# Sheet1.net
KiCad netlist of a schematic drawn in Altium Designer
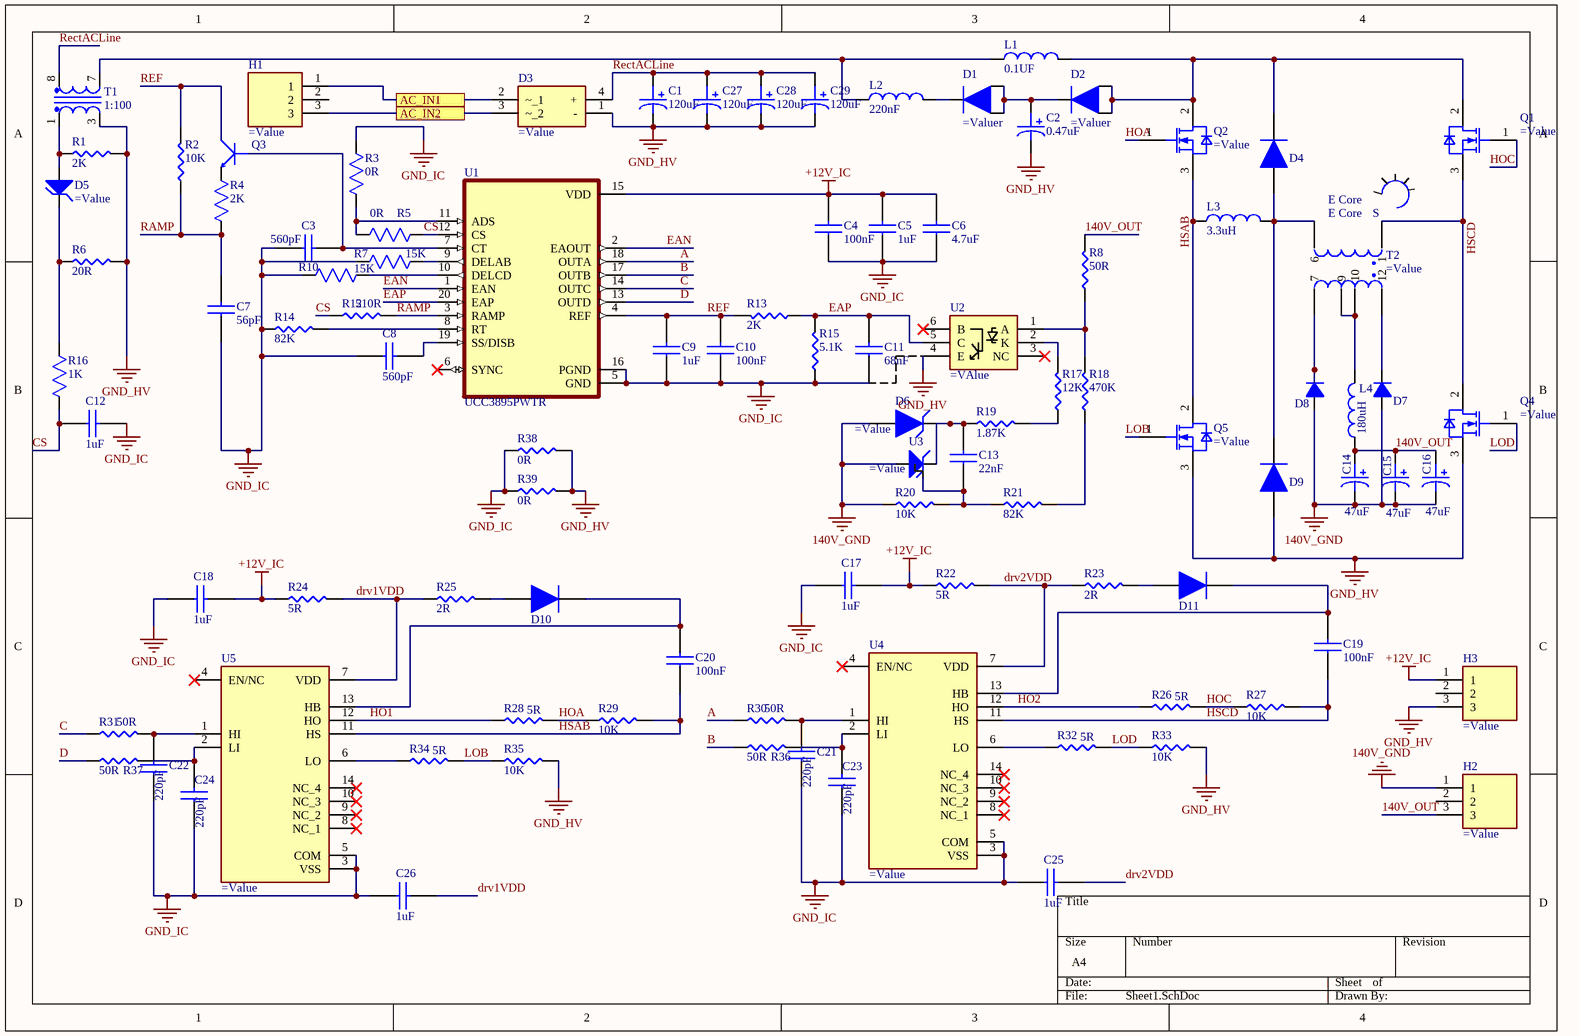
[diagram p0: Sheet1.SchDoc]

(export (version "E")
  (design (tool "Eeschema 10.0.6"))
  (components
    (comp (ref "C1")
      (value "120uF")
      (footprint "18AL_CAP")
      (description "120 µF 400 V Aluminum Electrolytic Capacitors Radial, Can 12000 Hrs @ 105°C")
      (fields
        (field (name "MANUFACTURER") "Nichicon")
        (field (name "MANUFACTURER PART NUMBER") "EEV686M035A9HAA")
      )
      (libsource (lib "Yunus") (part "CAP_Pol"))
    )
    (comp (ref "C2")
      (value "0.47uF")
      (footprint "860021373001_PCB")
      (description "0.47 µF 400 V Aluminum Electrolytic Capacitors Radial, Can 2000 Hrs @ 105°C")
      (fields
        (field (name "MANUFACTURER") "Würth Elektronik")
        (field (name "MANUFACTURER PART NUMBER") "EEV686M035A9HAA")
      )
      (libsource (lib "Yunus") (part "CAP_Pol"))
    )
    (comp (ref "C3")
      (value "560pF")
      (footprint "CAP_0805")
      (description "Cap.,SMD,0805,NP0,560pF,5%,100V")
      (fields
        (field (name "MANUFACTURER") "Aillen")
        (field (name "MANUFACTURER PART NUMBER") "CL21B105KBFNNNE")
        (field (name "DESIGNED BY") "BERK")
      )
      (libsource (lib "Yunus") (part "CAP_non"))
    )
    (comp (ref "C4")
      (value "100nF")
      (footprint "CAP_0805")
      (description "Auto. MLCC X7R 100nF 10% 100V 08")
      (fields
        (field (name "MANUFACTURER") "EYang Technology")
        (field (name "MANUFACTURER PART NUMBER") "CL21B105KBFNNNE")
        (field (name "DESIGNED BY") "BERK")
      )
      (libsource (lib "Yunus") (part "CAP_non"))
    )
    (comp (ref "C5")
      (value "1uF")
      (footprint "CAP_0805")
      (description "CAP SMD,0805,X7R,1UF,10%,50V")
      (fields
        (field (name "MANUFACTURER") "Aillen")
        (field (name "MANUFACTURER PART NUMBER") "CL21B105KBFNNNE")
        (field (name "DESIGNED BY") "BERK")
      )
      (libsource (lib "Yunus") (part "CAP_non"))
    )
    (comp (ref "C6")
      (value "4.7uF")
      (footprint "CAP_0805")
      (description "CAP,SMD,0805,X7R,4.7UF,10%,25V")
      (fields
        (field (name "MANUFACTURER") "NextGen Components")
        (field (name "MANUFACTURER PART NUMBER") "CL21B105KBFNNNE")
        (field (name "DESIGNED BY") "BERK")
      )
      (libsource (lib "Yunus") (part "CAP_non"))
    )
    (comp (ref "C7")
      (value "56pF")
      (footprint "CAP_0805")
      (description "CAP,SMD,0805,NP0,56PF,5%,50V")
      (fields
        (field (name "MANUFACTURER") "NextGen Components")
        (field (name "MANUFACTURER PART NUMBER") "CL21B105KBFNNNE")
        (field (name "DESIGNED BY") "BERK")
      )
      (libsource (lib "Yunus") (part "CAP_non"))
    )
    (comp (ref "C8")
      (value "560pF")
      (footprint "CAP_0805")
      (description "Cap.,SMD,0805,NP0,560pF,5%,100V")
      (fields
        (field (name "MANUFACTURER") "Aillen")
        (field (name "MANUFACTURER PART NUMBER") "CL21B105KBFNNNE")
        (field (name "DESIGNED BY") "BERK")
      )
      (libsource (lib "Yunus") (part "CAP_non"))
    )
    (comp (ref "C9")
      (value "1uF")
      (footprint "CAP_0805")
      (description "CAP SMD,0805,X7R,1UF,10%,50V")
      (fields
        (field (name "MANUFACTURER") "Aillen")
        (field (name "MANUFACTURER PART NUMBER") "CL21B105KBFNNNE")
        (field (name "DESIGNED BY") "BERK")
      )
      (libsource (lib "Yunus") (part "CAP_non"))
    )
    (comp (ref "C10")
      (value "100nF")
      (footprint "CAP_0805")
      (description "Auto. MLCC X7R 100nF 10% 100V 08")
      (fields
        (field (name "MANUFACTURER") "EYang Technology")
        (field (name "MANUFACTURER PART NUMBER") "CL21B105KBFNNNE")
        (field (name "DESIGNED BY") "BERK")
      )
      (libsource (lib "Yunus") (part "CAP_non"))
    )
    (comp (ref "C11")
      (value "68nF")
      (footprint "CAP_0805")
      (description "CAP CER 0805 68NF 50V X7R 10%")
      (fields
        (field (name "MANUFACTURER") "KEMET")
        (field (name "MANUFACTURER PART NUMBER") "CL21B105KBFNNNE")
        (field (name "DESIGNED BY") "BERK")
      )
      (libsource (lib "Yunus") (part "CAP_non"))
    )
    (comp (ref "C12")
      (value "1uF")
      (footprint "CAP_0805")
      (description "CAP SMD,0805,X7R,1UF,10%,50V")
      (fields
        (field (name "MANUFACTURER") "Aillen")
        (field (name "MANUFACTURER PART NUMBER") "CL21B105KBFNNNE")
        (field (name "DESIGNED BY") "BERK")
      )
      (libsource (lib "Yunus") (part "CAP_non"))
    )
    (comp (ref "C13")
      (value "22nF")
      (footprint "CAP_0805")
      (description "CAP CER 0805 22NF 200V X7R 10%")
      (fields
        (field (name "MANUFACTURER") "KEMET")
        (field (name "MANUFACTURER PART NUMBER") "CL21B105KBFNNNE")
        (field (name "DESIGNED BY") "BERK")
      )
      (libsource (lib "Yunus") (part "CAP_non"))
    )
    (comp (ref "C14")
      (value "47uF")
      (footprint "CAP200V47uF")
      (description "CAP ALUM 47UF 20% 200V RADIAL TH")
      (fields
        (field (name "MANUFACTURER") "KYOCERA AVX")
        (field (name "MANUFACTURER PART NUMBER") "EEV686M035A9HAA")
      )
      (libsource (lib "Yunus") (part "CAP_Pol"))
    )
    (comp (ref "C15")
      (value "47uF")
      (footprint "CAP200V47uF")
      (description "CAP ALUM 47UF 20% 200V RADIAL TH")
      (fields
        (field (name "MANUFACTURER") "KYOCERA AVX")
        (field (name "MANUFACTURER PART NUMBER") "EEV686M035A9HAA")
      )
      (libsource (lib "Yunus") (part "CAP_Pol"))
    )
    (comp (ref "C16")
      (value "47uF")
      (footprint "CAP200V47uF")
      (description "CAP ALUM 47UF 20% 200V RADIAL TH")
      (fields
        (field (name "MANUFACTURER") "KYOCERA AVX")
        (field (name "MANUFACTURER PART NUMBER") "EEV686M035A9HAA")
      )
      (libsource (lib "Yunus") (part "CAP_Pol"))
    )
    (comp (ref "C17")
      (value "1uF")
      (footprint "CAP_0805")
      (description "CAP SMD,0805,X7R,1UF,10%,50V")
      (fields
        (field (name "MANUFACTURER") "Aillen")
        (field (name "MANUFACTURER PART NUMBER") "CL21B105KBFNNNE")
        (field (name "DESIGNED BY") "BERK")
      )
      (libsource (lib "Yunus") (part "CAP_non"))
    )
    (comp (ref "C18")
      (value "1uF")
      (footprint "CAP_0805")
      (description "CAP SMD,0805,X7R,1UF,10%,50V")
      (fields
        (field (name "MANUFACTURER") "Aillen")
        (field (name "MANUFACTURER PART NUMBER") "CL21B105KBFNNNE")
        (field (name "DESIGNED BY") "BERK")
      )
      (libsource (lib "Yunus") (part "CAP_non"))
    )
    (comp (ref "C19")
      (value "100nF")
      (footprint "CAP_0805")
      (description "Auto. MLCC X7R 100nF 10% 100V 08")
      (fields
        (field (name "MANUFACTURER") "EYang Technology")
        (field (name "MANUFACTURER PART NUMBER") "CL21B105KBFNNNE")
        (field (name "DESIGNED BY") "BERK")
      )
      (libsource (lib "Yunus") (part "CAP_non"))
    )
    (comp (ref "C20")
      (value "100nF")
      (footprint "CAP_0805")
      (description "Auto. MLCC X7R 100nF 10% 100V 08")
      (fields
        (field (name "MANUFACTURER") "EYang Technology")
        (field (name "MANUFACTURER PART NUMBER") "CL21B105KBFNNNE")
        (field (name "DESIGNED BY") "BERK")
      )
      (libsource (lib "Yunus") (part "CAP_non"))
    )
    (comp (ref "C21")
      (value "220pF")
      (footprint "CAP_0805")
      (description "CAP CER 220PF 250V C0G/NP0 0805")
      (fields
        (field (name "MANUFACTURER") "KYOCERA AVX")
        (field (name "MANUFACTURER PART NUMBER") "CL21B105KBFNNNE")
        (field (name "DESIGNED BY") "BERK")
      )
      (libsource (lib "Yunus") (part "CAP_non"))
    )
    (comp (ref "C22")
      (value "220pF")
      (footprint "CAP_0805")
      (description "CAP CER 220PF 250V C0G/NP0 0805")
      (fields
        (field (name "MANUFACTURER") "KYOCERA AVX")
        (field (name "MANUFACTURER PART NUMBER") "CL21B105KBFNNNE")
        (field (name "DESIGNED BY") "BERK")
      )
      (libsource (lib "Yunus") (part "CAP_non"))
    )
    (comp (ref "C23")
      (value "220pF")
      (footprint "CAP_0805")
      (description "CAP CER 220PF 250V C0G/NP0 0805")
      (fields
        (field (name "MANUFACTURER") "KYOCERA AVX")
        (field (name "MANUFACTURER PART NUMBER") "CL21B105KBFNNNE")
        (field (name "DESIGNED BY") "BERK")
      )
      (libsource (lib "Yunus") (part "CAP_non"))
    )
    (comp (ref "C24")
      (value "220pF")
      (footprint "CAP_0805")
      (description "CAP CER 220PF 250V C0G/NP0 0805")
      (fields
        (field (name "MANUFACTURER") "KYOCERA AVX")
        (field (name "MANUFACTURER PART NUMBER") "CL21B105KBFNNNE")
        (field (name "DESIGNED BY") "BERK")
      )
      (libsource (lib "Yunus") (part "CAP_non"))
    )
    (comp (ref "C25")
      (value "1uF")
      (footprint "CAP_0805")
      (description "CAP SMD,0805,X7R,1UF,10%,50V")
      (fields
        (field (name "MANUFACTURER") "Aillen")
        (field (name "MANUFACTURER PART NUMBER") "CL21B105KBFNNNE")
        (field (name "DESIGNED BY") "BERK")
      )
      (libsource (lib "Yunus") (part "CAP_non"))
    )
    (comp (ref "C26")
      (value "1uF")
      (footprint "CAP_0805")
      (description "CAP SMD,0805,X7R,1UF,10%,50V")
      (fields
        (field (name "MANUFACTURER") "Aillen")
        (field (name "MANUFACTURER PART NUMBER") "CL21B105KBFNNNE")
        (field (name "DESIGNED BY") "BERK")
      )
      (libsource (lib "Yunus") (part "CAP_non"))
    )
    (comp (ref "C27")
      (value "120uF")
      (footprint "18AL_CAP")
      (description "120 µF 400 V Aluminum Electrolytic Capacitors Radial, Can 12000 Hrs @ 105°C")
      (fields
        (field (name "MANUFACTURER") "Nichicon")
        (field (name "MANUFACTURER PART NUMBER") "EEV686M035A9HAA")
      )
      (libsource (lib "Yunus") (part "CAP_Pol"))
    )
    (comp (ref "C28")
      (value "120uF")
      (footprint "18AL_CAP")
      (description "120 µF 400 V Aluminum Electrolytic Capacitors Radial, Can 12000 Hrs @ 105°C")
      (fields
        (field (name "MANUFACTURER") "Nichicon")
        (field (name "MANUFACTURER PART NUMBER") "EEV686M035A9HAA")
      )
      (libsource (lib "Yunus") (part "CAP_Pol"))
    )
    (comp (ref "C29")
      (value "120uF")
      (footprint "18AL_CAP")
      (description "120 µF 400 V Aluminum Electrolytic Capacitors Radial, Can 12000 Hrs @ 105°C")
      (fields
        (field (name "MANUFACTURER") "Nichicon")
        (field (name "MANUFACTURER PART NUMBER") "EEV686M035A9HAA")
      )
      (libsource (lib "Yunus") (part "CAP_Pol"))
    )
    (comp (ref "D1")
      (value "~")
      (footprint "DPAK(TO-252-2)")
      (description "DIODE STANDARD 600V 20A DPAK")
      (fields (field (name "MANUFACTURER") "SMC Diode Solutions"))
      (libsource (lib "Yunus") (part "DIODE(DPAC)"))
    )
    (comp (ref "D2")
      (value "~")
      (footprint "DPAK(TO-252-2)")
      (description "DIODE STANDARD 600V 20A DPAK")
      (fields (field (name "MANUFACTURER") "SMC Diode Solutions"))
      (libsource (lib "Yunus") (part "DIODE(DPAC)"))
    )
    (comp (ref "D3")
      (value "~")
      (footprint "4-SIP")
      (description "Bridge Rectifier Single Phase Standard 1 kV Through Hole GBU")
      (fields (field (name "MANUFACTURER") "MCC (Micro Commercial Components)"))
      (libsource (lib "Yunus") (part "Diode_Rectifire"))
    )
    (comp (ref "D4")
      (value "~")
      (footprint "DO-214AB(SMC)")
      (description "Diode 600 V 3A Surface Mount SMC")
      (fields (field (name "MANUFACTURER") "onsemi") (field (name "DESIGNED BY") "Yunus"))
      (libsource (lib "Yunus") (part "Diode"))
    )
    (comp (ref "D5")
      (value "~")
      (footprint "SOD123")
      (description "Diode 30 V 200mA Surface Mount SOD-123")
      (fields (field (name "MANUFACTURER") "onsemi"))
      (libsource (lib "Yunus") (part "TVS Diode"))
    )
    (comp (ref "D6")
      (value "~")
      (footprint "DO_214AA")
      (description "DIODE ZENER 140V 5W DO214AA")
      (fields
        (field (name "MANUFACTURER") "MCC (Micro Commercial Components)")
        (field (name "MANUFACTURER PART NUMBER") "9BT3G")
      )
      (libsource (lib "Yunus") (part "Zener Diode"))
    )
    (comp (ref "D7")
      (value "~")
      (footprint "DPAK(TO-252-2)")
      (description "DIODE SCHOTTKY 1200V 5A DPAK")
      (fields (field (name "MANUFACTURER") "SMC Diode Solutions"))
      (libsource (lib "Yunus") (part "S4D05120E1(SCHOTTKY Diode)"))
    )
    (comp (ref "D8")
      (value "~")
      (footprint "DPAK(TO-252-2)")
      (description "DIODE SCHOTTKY 1200V 5A DPAK")
      (fields (field (name "MANUFACTURER") "SMC Diode Solutions"))
      (libsource (lib "Yunus") (part "S4D05120E1(SCHOTTKY Diode)"))
    )
    (comp (ref "D9")
      (value "~")
      (footprint "DO-214AB(SMC)")
      (description "Diode 600 V 3A Surface Mount SMC")
      (fields (field (name "MANUFACTURER") "onsemi") (field (name "DESIGNED BY") "Yunus"))
      (libsource (lib "Yunus") (part "Diode"))
    )
    (comp (ref "D10")
      (value "~")
      (footprint "DO-214AB(SMC)")
      (description "Diode 600 V 3A Surface Mount SMC")
      (fields (field (name "MANUFACTURER") "onsemi") (field (name "DESIGNED BY") "Yunus"))
      (libsource (lib "Yunus") (part "Diode"))
    )
    (comp (ref "D11")
      (value "~")
      (footprint "DO-214AB(SMC)")
      (description "Diode 600 V 3A Surface Mount SMC")
      (fields (field (name "MANUFACTURER") "onsemi") (field (name "DESIGNED BY") "Yunus"))
      (libsource (lib "Yunus") (part "Diode"))
    )
    (comp (ref "H1")
      (value "~")
      (footprint "3 x 5.08 POS")
      (description "TERM BLOCK HDR 3POS 5.08MM")
      (fields (field (name "MANUFACTURER") "Same Sky (Formerly CUI Devices)"))
      (libsource (lib "") (part "3 X POS_1"))
    )
    (comp (ref "H2")
      (value "~")
      (footprint "3 x 5.08 POS")
      (description "TERM BLOCK HDR 3POS 5.08MM")
      (fields (field (name "MANUFACTURER") "Same Sky (Formerly CUI Devices)"))
      (libsource (lib "Yunus") (part "3 X POS"))
    )
    (comp (ref "H3")
      (value "~")
      (footprint "3 x 5.08 POS")
      (description "TERM BLOCK HDR 3POS 5.08MM")
      (fields (field (name "MANUFACTURER") "Same Sky (Formerly CUI Devices)"))
      (libsource (lib "Yunus") (part "3 X POS"))
    )
    (comp (ref "L1")
      (value "0.1UF")
      (footprint "7.30mm x 6.60mm")
      (description "100 nH Shielded Wirewound Inductor 37.5 A 1.7mOhm Max Nonstandard")
      (fields (field (name "MANUFACTURER") "Bourns Inc."))
      (libsource (lib "Yunus") (part "Enductance"))
    )
    (comp (ref "L2")
      (value "220nF")
      (footprint "7.30mm x 6.60mm")
      (description "220 nH Shielded Molded Inductor 23 A 2.8mOhm Max Nonstandard")
      (fields (field (name "MANUFACTURER") "Pulse Electronics"))
      (libsource (lib "Yunus") (part "Enductance"))
    )
    (comp (ref "L3")
      (value "3.3uH")
      (footprint "14.4MOHM SMD")
      (description "FIXED IND 3.3UH 10A 14.4MOHM SMD")
      (fields (field (name "MANUFACTURER") "Vishay Dale"))
      (libsource (lib "Yunus") (part "Enductance"))
    )
    (comp (ref "L4")
      (value "180uH")
      (footprint "2300HT-181-V-RC")
      (description "180 µH Shielded Toroidal Inductor 7.2 A 55mOhm Max Radial, Vertical (Open)")
      (fields (field (name "MANUFACTURER") "Bourns Inc."))
      (libsource (lib "Yunus") (part "Enductance"))
    )
    (comp (ref "Q1")
      (value "~")
      (footprint "TO220")
      (description "N-Channel 650 V 25A (Tc) 32W (Tc) Through Hole PG-TO220-FP")
      (fields (field (name "MANUFACTURER") "Infineon Technologies"))
      (libsource (lib "Yunus") (part "N_MOS"))
    )
    (comp (ref "Q2")
      (value "~")
      (footprint "TO220")
      (description "N-Channel 650 V 25A (Tc) 32W (Tc) Through Hole PG-TO220-FP")
      (fields (field (name "MANUFACTURER") "Infineon Technologies"))
      (libsource (lib "Yunus") (part "N_MOS"))
    )
    (comp (ref "Q3")
      (value "~")
      (footprint "SOT-23-3")
      (description "TRANS NPN 80V 0.5A SOT-23-3")
      (fields (field (name "MANUFACTURER") "Diodes Incorporated") (field (name "DESIGNED BY") "YYunus"))
      (libsource (lib "Yunus") (part "NPN Transistor"))
    )
    (comp (ref "Q4")
      (value "~")
      (footprint "TO220")
      (description "N-Channel 650 V 25A (Tc) 32W (Tc) Through Hole PG-TO220-FP")
      (fields (field (name "MANUFACTURER") "Infineon Technologies"))
      (libsource (lib "Yunus") (part "N_MOS"))
    )
    (comp (ref "Q5")
      (value "~")
      (footprint "TO220")
      (description "N-Channel 650 V 25A (Tc) 32W (Tc) Through Hole PG-TO220-FP")
      (fields (field (name "MANUFACTURER") "Infineon Technologies"))
      (libsource (lib "Yunus") (part "N_MOS"))
    )
    (comp (ref "R1")
      (value "2K")
      (footprint "RES_0805")
      (description "RES SMD 2K OHM 0.1% 1/8W 0805")
      (fields (field (name "MANUFACTURER") "Panasonic Electronic Components"))
      (libsource (lib "Yunus") (part "RES"))
    )
    (comp (ref "R2")
      (value "10K")
      (footprint "RES_0805")
      (description "RES SMD 10K OHM 0.5% 1/10W 0805")
      (fields (field (name "MANUFACTURER") "Susumu"))
      (libsource (lib "Yunus") (part "RES"))
    )
    (comp (ref "R3")
      (value "0R")
      (footprint "RES_0805")
      (description "RES SMD 0 OHM JUMPER 1/8W 0805")
      (fields (field (name "MANUFACTURER") "Panasonic Electronic Components"))
      (libsource (lib "") (part "RES_1"))
    )
    (comp (ref "R4")
      (value "2K")
      (footprint "RES_0805")
      (description "RES SMD 2K OHM 0.1% 1/8W 0805")
      (fields (field (name "MANUFACTURER") "Panasonic Electronic Components"))
      (libsource (lib "") (part "RES_1"))
    )
    (comp (ref "R5")
      (value "0R")
      (footprint "RES_0805")
      (description "RES SMD 0 OHM JUMPER 1/8W 0805")
      (fields (field (name "MANUFACTURER") "Panasonic Electronic Components"))
      (libsource (lib "") (part "RES_1"))
    )
    (comp (ref "R6")
      (value "20R")
      (footprint "RES_0805")
      (description "RES SMD 20 OHM 0.5% 1/4W 0805")
      (fields (field (name "MANUFACTURER") "Stackpole Electronics Inc"))
      (libsource (lib "Yunus") (part "RES"))
    )
    (comp (ref "R7")
      (value "15K")
      (footprint "RES_0805")
      (description "RES SMD 15K OHM 5% 1/8W 0805")
      (fields (field (name "MANUFACTURER") "Meritek"))
      (libsource (lib "") (part "RES_1"))
    )
    (comp (ref "R8")
      (value "50R")
      (footprint "RES_0805")
      (description "CRCW0805 50 1% 100 RT1")
      (fields (field (name "MANUFACTURER") "Vishay Dale"))
      (libsource (lib "Yunus") (part "RES"))
    )
    (comp (ref "R10")
      (value "15K")
      (footprint "RES_0805")
      (description "RES SMD 15K OHM 5% 1/8W 0805")
      (fields (field (name "MANUFACTURER") "Meritek"))
      (libsource (lib "") (part "RES_1"))
    )
    (comp (ref "R12")
      (value "510R")
      (footprint "RES_0805")
      (description "RES 510 OHM 5% 1/8W 0805")
      (fields (field (name "MANUFACTURER") "Stackpole Electronics Inc"))
      (libsource (lib "Yunus") (part "RES"))
    )
    (comp (ref "R13")
      (value "2K")
      (footprint "RES_0805")
      (description "RES SMD 2K OHM 0.1% 1/8W 0805")
      (fields (field (name "MANUFACTURER") "Panasonic Electronic Components"))
      (libsource (lib "Yunus") (part "RES"))
    )
    (comp (ref "R14")
      (value "82K")
      (footprint "RES_0805")
      (description "RES 82K OHM 1% 1/4W 0805")
      (fields (field (name "MANUFACTURER") "KOA Speer Electronics, Inc."))
      (libsource (lib "Yunus") (part "RES"))
    )
    (comp (ref "R15")
      (value "5.1K")
      (footprint "RES_0805")
      (description "RES 5.1K OHM 5% 1/8W 0805")
      (fields (field (name "MANUFACTURER") "YAGEO"))
      (libsource (lib "Yunus") (part "RES"))
    )
    (comp (ref "R16")
      (value "1K")
      (footprint "RES_0805")
      (description "RES SMD 1K OHM 0.5% 1/10W 0805")
      (fields (field (name "MANUFACTURER") "Susumu"))
      (libsource (lib "") (part "RES_1"))
    )
    (comp (ref "R17")
      (value "12K")
      (footprint "RES_0805")
      (description "RES 12K OHM 5% 1/8W 0805")
      (fields (field (name "MANUFACTURER") "Stackpole Electronics Inc"))
      (libsource (lib "Yunus") (part "RES"))
    )
    (comp (ref "R18")
      (value "470K")
      (footprint "RES_0805")
      (description "RES 470K OHM 1% 1/8W 0805")
      (fields (field (name "MANUFACTURER") "YAGEO"))
      (libsource (lib "Yunus") (part "RES"))
    )
    (comp (ref "R19")
      (value "1.87K")
      (footprint "RES_0603")
      (description "RES SMD 1.87K OHM 1% 1/20W 0201")
      (fields (field (name "MANUFACTURER") "Panasonic Electronic Components"))
      (libsource (lib "Yunus") (part "RES"))
    )
    (comp (ref "R20")
      (value "10K")
      (footprint "RES_0805")
      (description "RES SMD 10K OHM 0.5% 1/10W 0805")
      (fields (field (name "MANUFACTURER") "Susumu"))
      (libsource (lib "Yunus") (part "RES"))
    )
    (comp (ref "R21")
      (value "82K")
      (footprint "RES_0805")
      (description "RES 82K OHM 1% 1/4W 0805")
      (fields (field (name "MANUFACTURER") "KOA Speer Electronics, Inc."))
      (libsource (lib "Yunus") (part "RES"))
    )
    (comp (ref "R22")
      (value "5R")
      (footprint "RES_0805")
      (description "RES SMD 5 OHM 1% 1/5W 0805")
      (fields (field (name "MANUFACTURER") "VPG Foil Resistors"))
      (libsource (lib "Yunus") (part "RES"))
    )
    (comp (ref "R23")
      (value "2R")
      (footprint "RES_0805")
      (description "RES 2 OHM 1% 1/8W 0805")
      (fields (field (name "MANUFACTURER") "YAGEO"))
      (libsource (lib "Yunus") (part "RES"))
    )
    (comp (ref "R24")
      (value "5R")
      (footprint "RES_0805")
      (description "RES SMD 5 OHM 1% 1/5W 0805")
      (fields (field (name "MANUFACTURER") "VPG Foil Resistors"))
      (libsource (lib "Yunus") (part "RES"))
    )
    (comp (ref "R25")
      (value "2R")
      (footprint "RES_0805")
      (description "RES 2 OHM 1% 1/8W 0805")
      (fields (field (name "MANUFACTURER") "YAGEO"))
      (libsource (lib "Yunus") (part "RES"))
    )
    (comp (ref "R26")
      (value "5R")
      (footprint "RES_0805")
      (description "RES SMD 5 OHM 1% 1/5W 0805")
      (fields (field (name "MANUFACTURER") "VPG Foil Resistors"))
      (libsource (lib "Yunus") (part "RES"))
    )
    (comp (ref "R27")
      (value "10K")
      (footprint "RES_0805")
      (description "RES SMD 10K OHM 0.5% 1/10W 0805")
      (fields (field (name "MANUFACTURER") "Susumu"))
      (libsource (lib "Yunus") (part "RES"))
    )
    (comp (ref "R28")
      (value "5R")
      (footprint "RES_0805")
      (description "RES SMD 5 OHM 1% 1/5W 0805")
      (fields (field (name "MANUFACTURER") "VPG Foil Resistors"))
      (libsource (lib "Yunus") (part "RES"))
    )
    (comp (ref "R29")
      (value "10K")
      (footprint "RES_0805")
      (description "RES SMD 10K OHM 0.5% 1/10W 0805")
      (fields (field (name "MANUFACTURER") "Susumu"))
      (libsource (lib "Yunus") (part "RES"))
    )
    (comp (ref "R30")
      (value "50R")
      (footprint "RES_0805")
      (description "CRCW0805 50 1% 100 RT1")
      (fields (field (name "MANUFACTURER") "Vishay Dale"))
      (libsource (lib "Yunus") (part "RES"))
    )
    (comp (ref "R31")
      (value "50R")
      (footprint "RES_0805")
      (description "CRCW0805 50 1% 100 RT1")
      (fields (field (name "MANUFACTURER") "Vishay Dale"))
      (libsource (lib "Yunus") (part "RES"))
    )
    (comp (ref "R32")
      (value "5R")
      (footprint "RES_0805")
      (description "RES SMD 5 OHM 1% 1/5W 0805")
      (fields (field (name "MANUFACTURER") "VPG Foil Resistors"))
      (libsource (lib "Yunus") (part "RES"))
    )
    (comp (ref "R33")
      (value "10K")
      (footprint "RES_0805")
      (description "RES SMD 10K OHM 0.5% 1/10W 0805")
      (fields (field (name "MANUFACTURER") "Susumu"))
      (libsource (lib "Yunus") (part "RES"))
    )
    (comp (ref "R34")
      (value "5R")
      (footprint "RES_0805")
      (description "RES SMD 5 OHM 1% 1/5W 0805")
      (fields (field (name "MANUFACTURER") "VPG Foil Resistors"))
      (libsource (lib "Yunus") (part "RES"))
    )
    (comp (ref "R35")
      (value "10K")
      (footprint "RES_0805")
      (description "RES SMD 10K OHM 0.5% 1/10W 0805")
      (fields (field (name "MANUFACTURER") "Susumu"))
      (libsource (lib "Yunus") (part "RES"))
    )
    (comp (ref "R36")
      (value "50R")
      (footprint "RES_0805")
      (description "CRCW0805 50 1% 100 RT1")
      (fields (field (name "MANUFACTURER") "Vishay Dale"))
      (libsource (lib "Yunus") (part "RES"))
    )
    (comp (ref "R37")
      (value "50R")
      (footprint "RES_0805")
      (description "CRCW0805 50 1% 100 RT1")
      (fields (field (name "MANUFACTURER") "Vishay Dale"))
      (libsource (lib "Yunus") (part "RES"))
    )
    (comp (ref "R38")
      (value "0R")
      (footprint "RES_0805")
      (description "RES SMD 0 OHM JUMPER 1/8W 0805")
      (fields (field (name "MANUFACTURER") "Panasonic Electronic Components"))
      (libsource (lib "Yunus") (part "RES"))
    )
    (comp (ref "R39")
      (value "0R")
      (footprint "RES_0805")
      (description "RES SMD 0 OHM JUMPER 1/8W 0805")
      (fields (field (name "MANUFACTURER") "Panasonic Electronic Components"))
      (libsource (lib "Yunus") (part "RES"))
    )
    (comp (ref "S")
      (value "~")
      (footprint "Sogutucu60x90")
      (description "981AS90 AL.SOĞUTUCU")
      (fields (field (name "MANUFACTURER") "ARMA"))
      (libsource (lib "Yunus") (part "Sogutucu"))
    )
    (comp (ref "T1")
      (value "1:100")
      (footprint "PA1005.100QNLT")
      (description "CURR SENSE XFMR 1:100 20A SMD")
      (fields (field (name "MANUFACTURER") "Pulse Electronics"))
      (libsource (lib "Yunus") (part "PA1005"))
    )
    (comp (ref "T2")
      (value "~")
      (footprint "FE0270")
      (description "BOBBIN COIL FORMER E 55X28X21")
      (fields (field (name "MANUFACTURER") "Miles Platts Ltd"))
      (libsource (lib "Yunus") (part "Trafo"))
    )
    (comp (ref "U1")
      (value "UCC3895PWTR")
      (footprint "20-SOIC")
      (description "IC OFFLINE SW FULL-BRDG 20SOIC")
      (fields (field (name "MANUFACTURER") "Texas Instruments"))
      (libsource (lib "Yunus") (part "UCC3895"))
    )
    (comp (ref "U2")
      (value "~")
      (footprint "CNY172SM_FP")
      (description "OPTOISO 4.17KV TRANS W/BASE 6SMD")
      (fields (field (name "MANUFACTURER") "onsemi"))
      (libsource (lib "Yunus") (part "CNY172SM_SC"))
    )
    (comp (ref "U3")
      (value "~")
      (footprint "SOT-23-3")
      (description "IC VREF SHUNT ADJ 1% SOT23-3")
      (fields (field (name "MANUFACTURER") "Texas Instruments"))
      (libsource (lib "Yunus") (part "LDO"))
    )
    (comp (ref "U4")
      (value "~")
      (footprint "14-SOP")
      (description "Half-Bridge Gate Driver IC Non-Inverting 14-SOP")
      (fields (field (name "MANUFACTURER") "UMW"))
      (libsource (lib "Yunus") (part "UCC27714DR"))
    )
    (comp (ref "U5")
      (value "~")
      (footprint "14-SOP")
      (description "Half-Bridge Gate Driver IC Non-Inverting 14-SOP")
      (fields (field (name "MANUFACTURER") "UMW"))
      (libsource (lib "Yunus") (part "UCC27714DR"))
    )
  )
  (nets
    (net (code "1") (name "+12V_IC") (class "Default")
      (node (ref "C17") (pin "2") (pinfunction "2_2") (pintype "passive"))
      (node (ref "C18") (pin "2") (pinfunction "2_2") (pintype "passive"))
      (node (ref "C4") (pin "2") (pinfunction "2_2") (pintype "passive"))
      (node (ref "C5") (pin "2") (pinfunction "2_2") (pintype "passive"))
      (node (ref "C6") (pin "2") (pinfunction "2_2") (pintype "passive"))
      (node (ref "H3") (pin "1") (pinfunction "1_1") (pintype "passive"))
      (node (ref "R22") (pin "1") (pinfunction "1_1") (pintype "passive"))
      (node (ref "R24") (pin "1") (pinfunction "1_1") (pintype "passive"))
      (node (ref "U1") (pin "15") (pinfunction "VDD_15") (pintype "power_in"))
    )
    (net (code "2") (name "/140V_OUT") (class "Default")
      (node (ref "C14") (pin "1") (pinfunction "1_1") (pintype "passive"))
      (node (ref "C15") (pin "1") (pinfunction "1_1") (pintype "passive"))
      (node (ref "C16") (pin "1") (pinfunction "1_1") (pintype "passive"))
      (node (ref "H2") (pin "3") (pinfunction "3_3") (pintype "passive"))
      (node (ref "L4") (pin "1") (pinfunction "1_1") (pintype "passive"))
      (node (ref "R8") (pin "2") (pinfunction "2_2") (pintype "passive"))
    )
    (net (code "3") (name "/A") (class "Default")
      (node (ref "R30") (pin "1") (pinfunction "1_1") (pintype "passive"))
      (node (ref "U1") (pin "18") (pinfunction "OUTA_18") (pintype "output"))
    )
    (net (code "4") (name "/AC_IN1") (class "Default")
      (node (ref "D3") (pin "2") (pinfunction "~_1_2") (pintype "passive"))
      (node (ref "H1") (pin "1") (pinfunction "1_1") (pintype "passive"))
    )
    (net (code "5") (name "/AC_IN2") (class "Default")
      (node (ref "D3") (pin "3") (pinfunction "~_2_3") (pintype "passive"))
      (node (ref "H1") (pin "3") (pinfunction "3_3") (pintype "passive"))
    )
    (net (code "6") (name "/B") (class "Default")
      (node (ref "R36") (pin "1") (pinfunction "1_1") (pintype "passive"))
      (node (ref "U1") (pin "17") (pinfunction "OUTB_17") (pintype "output"))
    )
    (net (code "7") (name "/C") (class "Default")
      (node (ref "R31") (pin "1") (pinfunction "1_1") (pintype "passive"))
      (node (ref "U1") (pin "14") (pinfunction "OUTC_14") (pintype "output"))
    )
    (net (code "8") (name "/CS") (class "Default")
      (node (ref "C12") (pin "1") (pinfunction "1_1") (pintype "passive"))
      (node (ref "R12") (pin "1") (pinfunction "1_1") (pintype "passive"))
      (node (ref "R16") (pin "1") (pinfunction "1_1") (pintype "passive"))
      (node (ref "R5") (pin "2") (pinfunction "2_2") (pintype "passive"))
      (node (ref "U1") (pin "12") (pinfunction "CS_12") (pintype "input"))
    )
    (net (code "9") (name "/D") (class "Default")
      (node (ref "R37") (pin "1") (pinfunction "1_1") (pintype "passive"))
      (node (ref "U1") (pin "13") (pinfunction "OUTD_13") (pintype "output"))
    )
    (net (code "10") (name "/EAN") (class "Default")
      (node (ref "U1") (pin "1") (pinfunction "EAN_1") (pintype "input"))
      (node (ref "U1") (pin "2") (pinfunction "EAOUT_2") (pintype "output"))
    )
    (net (code "11") (name "/EAP") (class "Default")
      (node (ref "C11") (pin "2") (pinfunction "2_2") (pintype "passive"))
      (node (ref "R13") (pin "1") (pinfunction "1_1") (pintype "passive"))
      (node (ref "R15") (pin "2") (pinfunction "2_2") (pintype "passive"))
      (node (ref "U1") (pin "20") (pinfunction "EAP_20") (pintype "input"))
      (node (ref "U2") (pin "5") (pinfunction "C_5") (pintype "passive"))
    )
    (net (code "12") (name "/HO1") (class "Default")
      (node (ref "R28") (pin "1") (pinfunction "1_1") (pintype "passive"))
      (node (ref "U5") (pin "12") (pinfunction "HO_12") (pintype "passive"))
    )
    (net (code "13") (name "/HO2") (class "Default")
      (node (ref "R26") (pin "1") (pinfunction "1_1") (pintype "passive"))
      (node (ref "U4") (pin "12") (pinfunction "HO_12") (pintype "passive"))
    )
    (net (code "14") (name "/HOA") (class "Default")
      (node (ref "Q2") (pin "1") (pinfunction "GATE_1") (pintype "passive"))
      (node (ref "R28") (pin "2") (pinfunction "2_2") (pintype "passive"))
      (node (ref "R29") (pin "1") (pinfunction "1_1") (pintype "passive"))
    )
    (net (code "15") (name "/HOC") (class "Default")
      (node (ref "Q1") (pin "1") (pinfunction "GATE_1") (pintype "passive"))
      (node (ref "R26") (pin "2") (pinfunction "2_2") (pintype "passive"))
      (node (ref "R27") (pin "1") (pinfunction "1_1") (pintype "passive"))
    )
    (net (code "16") (name "/HSAB") (class "Default")
      (node (ref "C20") (pin "1") (pinfunction "1_1") (pintype "passive"))
      (node (ref "L3") (pin "1") (pinfunction "1_1") (pintype "passive"))
      (node (ref "Q2") (pin "3") (pinfunction "SOURCE_3") (pintype "passive"))
      (node (ref "Q5") (pin "2") (pinfunction "DRAIN_2") (pintype "passive"))
      (node (ref "R29") (pin "2") (pinfunction "2_2") (pintype "passive"))
      (node (ref "U5") (pin "11") (pinfunction "HS_11") (pintype "passive"))
    )
    (net (code "17") (name "/HSCD") (class "Default")
      (node (ref "C19") (pin "1") (pinfunction "1_1") (pintype "passive"))
      (node (ref "Q1") (pin "3") (pinfunction "SOURCE_3") (pintype "passive"))
      (node (ref "Q4") (pin "2") (pinfunction "DRAIN_2") (pintype "passive"))
      (node (ref "R27") (pin "2") (pinfunction "2_2") (pintype "passive"))
      (node (ref "T2") (pin "1") (pinfunction "1_1") (pintype "passive"))
      (node (ref "U4") (pin "11") (pinfunction "HS_11") (pintype "passive"))
    )
    (net (code "18") (name "/LOB") (class "Default")
      (node (ref "Q5") (pin "1") (pinfunction "GATE_1") (pintype "passive"))
      (node (ref "R34") (pin "2") (pinfunction "2_2") (pintype "passive"))
      (node (ref "R35") (pin "1") (pinfunction "1_1") (pintype "passive"))
    )
    (net (code "19") (name "/LOD") (class "Default")
      (node (ref "Q4") (pin "1") (pinfunction "GATE_1") (pintype "passive"))
      (node (ref "R32") (pin "2") (pinfunction "2_2") (pintype "passive"))
      (node (ref "R33") (pin "1") (pinfunction "1_1") (pintype "passive"))
    )
    (net (code "20") (name "/RAMP") (class "Default")
      (node (ref "C7") (pin "2") (pinfunction "2_2") (pintype "passive"))
      (node (ref "R12") (pin "2") (pinfunction "2_2") (pintype "passive"))
      (node (ref "R2") (pin "1") (pinfunction "1_1") (pintype "passive"))
      (node (ref "R4") (pin "1") (pinfunction "1_1") (pintype "passive"))
      (node (ref "U1") (pin "3") (pinfunction "RAMP_3") (pintype "input"))
    )
    (net (code "21") (name "/REF") (class "Default")
      (node (ref "C10") (pin "2") (pinfunction "2_2") (pintype "passive"))
      (node (ref "C9") (pin "2") (pinfunction "2_2") (pintype "passive"))
      (node (ref "Q3") (pin "3") (pinfunction "C_3") (pintype "power_in"))
      (node (ref "R13") (pin "2") (pinfunction "2_2") (pintype "passive"))
      (node (ref "R2") (pin "2") (pinfunction "2_2") (pintype "passive"))
      (node (ref "U1") (pin "4") (pinfunction "REF_4") (pintype "output"))
    )
    (net (code "22") (name "/RectACLine") (class "Default")
      (node (ref "C1") (pin "1") (pinfunction "1_1") (pintype "passive"))
      (node (ref "C27") (pin "1") (pinfunction "1_1") (pintype "passive"))
      (node (ref "C28") (pin "1") (pinfunction "1_1") (pintype "passive"))
      (node (ref "C29") (pin "1") (pinfunction "1_1") (pintype "passive"))
      (node (ref "D3") (pin "4") (pinfunction "+_4") (pintype "passive"))
      (node (ref "T1") (pin "8") (pinfunction "8_8") (pintype "passive"))
    )
    (net (code "23") (name "/drv1VDD") (class "Default")
      (node (ref "C26") (pin "2") (pinfunction "2_2") (pintype "passive"))
      (node (ref "R24") (pin "2") (pinfunction "2_2") (pintype "passive"))
      (node (ref "R25") (pin "1") (pinfunction "1_1") (pintype "passive"))
      (node (ref "U5") (pin "7") (pinfunction "VDD_7") (pintype "passive"))
    )
    (net (code "24") (name "/drv2VDD") (class "Default")
      (node (ref "C25") (pin "2") (pinfunction "2_2") (pintype "passive"))
      (node (ref "R22") (pin "2") (pinfunction "2_2") (pintype "passive"))
      (node (ref "R23") (pin "1") (pinfunction "1_1") (pintype "passive"))
      (node (ref "U4") (pin "7") (pinfunction "VDD_7") (pintype "passive"))
    )
    (net (code "25") (name "140V_GND") (class "Default")
      (node (ref "C14") (pin "2") (pinfunction "2_2") (pintype "passive"))
      (node (ref "C15") (pin "2") (pinfunction "2_2") (pintype "passive"))
      (node (ref "C16") (pin "2") (pinfunction "2_2") (pintype "passive"))
      (node (ref "D6") (pin "A") (pinfunction "A_A") (pintype "passive"))
      (node (ref "D7") (pin "3") (pinfunction "3_3") (pintype "power_in"))
      (node (ref "D8") (pin "3") (pinfunction "3_3") (pintype "power_in"))
      (node (ref "H2") (pin "1") (pinfunction "1_1") (pintype "passive"))
      (node (ref "R20") (pin "1") (pinfunction "1_1") (pintype "passive"))
      (node (ref "U3") (pin "2") (pinfunction "2_2") (pintype "passive"))
    )
    (net (code "26") (name "GND_HV") (class "Default")
      (node (ref "C1") (pin "2") (pinfunction "2_2") (pintype "passive"))
      (node (ref "C2") (pin "2") (pinfunction "2_2") (pintype "passive"))
      (node (ref "C27") (pin "2") (pinfunction "2_2") (pintype "passive"))
      (node (ref "C28") (pin "2") (pinfunction "2_2") (pintype "passive"))
      (node (ref "C29") (pin "2") (pinfunction "2_2") (pintype "passive"))
      (node (ref "D3") (pin "1") (pinfunction "-_1") (pintype "passive"))
      (node (ref "D9") (pin "2") (pinfunction "2_2") (pintype "power_in"))
      (node (ref "H3") (pin "3") (pinfunction "3_3") (pintype "passive"))
      (node (ref "Q4") (pin "3") (pinfunction "SOURCE_3") (pintype "passive"))
      (node (ref "Q5") (pin "3") (pinfunction "SOURCE_3") (pintype "passive"))
      (node (ref "R1") (pin "2") (pinfunction "2_2") (pintype "passive"))
      (node (ref "R33") (pin "2") (pinfunction "2_2") (pintype "passive"))
      (node (ref "R35") (pin "2") (pinfunction "2_2") (pintype "passive"))
      (node (ref "R38") (pin "2") (pinfunction "2_2") (pintype "passive"))
      (node (ref "R39") (pin "2") (pinfunction "2_2") (pintype "passive"))
      (node (ref "R6") (pin "2") (pinfunction "2_2") (pintype "passive"))
      (node (ref "T1") (pin "3") (pinfunction "3_3") (pintype "passive"))
      (node (ref "U2") (pin "4") (pinfunction "E_4") (pintype "passive"))
    )
    (net (code "27") (name "GND_IC") (class "Default")
      (node (ref "C10") (pin "1") (pinfunction "1_1") (pintype "passive"))
      (node (ref "C11") (pin "1") (pinfunction "1_1") (pintype "passive"))
      (node (ref "C12") (pin "2") (pinfunction "2_2") (pintype "passive"))
      (node (ref "C17") (pin "1") (pinfunction "1_1") (pintype "passive"))
      (node (ref "C18") (pin "1") (pinfunction "1_1") (pintype "passive"))
      (node (ref "C21") (pin "1") (pinfunction "1_1") (pintype "passive"))
      (node (ref "C22") (pin "1") (pinfunction "1_1") (pintype "passive"))
      (node (ref "C23") (pin "1") (pinfunction "1_1") (pintype "passive"))
      (node (ref "C24") (pin "1") (pinfunction "1_1") (pintype "passive"))
      (node (ref "C25") (pin "1") (pinfunction "1_1") (pintype "passive"))
      (node (ref "C26") (pin "1") (pinfunction "1_1") (pintype "passive"))
      (node (ref "C3") (pin "1") (pinfunction "1_1") (pintype "passive"))
      (node (ref "C4") (pin "1") (pinfunction "1_1") (pintype "passive"))
      (node (ref "C5") (pin "1") (pinfunction "1_1") (pintype "passive"))
      (node (ref "C6") (pin "1") (pinfunction "1_1") (pintype "passive"))
      (node (ref "C7") (pin "1") (pinfunction "1_1") (pintype "passive"))
      (node (ref "C8") (pin "1") (pinfunction "1_1") (pintype "passive"))
      (node (ref "C9") (pin "1") (pinfunction "1_1") (pintype "passive"))
      (node (ref "R10") (pin "1") (pinfunction "1_1") (pintype "passive"))
      (node (ref "R14") (pin "1") (pinfunction "1_1") (pintype "passive"))
      (node (ref "R15") (pin "1") (pinfunction "1_1") (pintype "passive"))
      (node (ref "R3") (pin "2") (pinfunction "2_2") (pintype "passive"))
      (node (ref "R38") (pin "1") (pinfunction "1_1") (pintype "passive"))
      (node (ref "R39") (pin "1") (pinfunction "1_1") (pintype "passive"))
      (node (ref "R7") (pin "1") (pinfunction "1_1") (pintype "passive"))
      (node (ref "U1") (pin "16") (pinfunction "PGND_16") (pintype "power_in"))
      (node (ref "U1") (pin "5") (pinfunction "GND_5") (pintype "power_in"))
      (node (ref "U4") (pin "3") (pinfunction "VSS_3") (pintype "passive"))
      (node (ref "U4") (pin "5") (pinfunction "COM_5") (pintype "passive"))
      (node (ref "U5") (pin "3") (pinfunction "VSS_3") (pintype "passive"))
      (node (ref "U5") (pin "5") (pinfunction "COM_5") (pintype "passive"))
    )
    (net (code "28") (name "Net-(C2-Pad1)") (class "Default")
      (node (ref "C2") (pin "1") (pinfunction "1_1") (pintype "passive"))
      (node (ref "D1") (pin "1") (pinfunction "1_1") (pintype "power_in"))
      (node (ref "D1") (pin "3") (pinfunction "3_3") (pintype "power_in"))
      (node (ref "D2") (pin "2") (pinfunction "2_2") (pintype "power_in"))
    )
    (net (code "29") (name "Net-(C13-Pad1)") (class "Default")
      (node (ref "C13") (pin "1") (pinfunction "1_1") (pintype "passive"))
      (node (ref "R20") (pin "2") (pinfunction "2_2") (pintype "passive"))
      (node (ref "R21") (pin "1") (pinfunction "1_1") (pintype "passive"))
      (node (ref "U3") (pin "1") (pinfunction "1_1") (pintype "passive"))
    )
    (net (code "30") (name "Net-(C13-Pad2)") (class "Default")
      (node (ref "C13") (pin "2") (pinfunction "2_2") (pintype "passive"))
      (node (ref "D6") (pin "C") (pinfunction "C_C") (pintype "passive"))
      (node (ref "R19") (pin "1") (pinfunction "1_1") (pintype "passive"))
      (node (ref "U3") (pin "3") (pinfunction "3_3") (pintype "passive"))
    )
    (net (code "31") (name "Net-(D1-Pad2)") (class "Default")
      (node (ref "D1") (pin "2") (pinfunction "2_2") (pintype "power_in"))
      (node (ref "L2") (pin "2") (pinfunction "2_2") (pintype "passive"))
    )
    (net (code "32") (name "Net-(D4-Pad2)") (class "Default")
      (node (ref "D4") (pin "2") (pinfunction "2_2") (pintype "power_in"))
      (node (ref "D9") (pin "1") (pinfunction "1_1") (pintype "power_in"))
      (node (ref "L3") (pin "2") (pinfunction "2_2") (pintype "passive"))
      (node (ref "T2") (pin "6") (pinfunction "6_6") (pintype "passive"))
    )
    (net (code "33") (name "Net-(D5-Pad1)") (class "Default")
      (node (ref "D5") (pin "1") (pinfunction "1_1") (pintype "passive"))
      (node (ref "R16") (pin "2") (pinfunction "2_2") (pintype "passive"))
      (node (ref "R6") (pin "1") (pinfunction "1_1") (pintype "passive"))
    )
    (net (code "34") (name "Net-(D5-Pad2)") (class "Default")
      (node (ref "D5") (pin "2") (pinfunction "2_2") (pintype "passive"))
      (node (ref "R1") (pin "1") (pinfunction "1_1") (pintype "passive"))
      (node (ref "T1") (pin "1") (pinfunction "1_1") (pintype "passive"))
    )
    (net (code "35") (name "Net-(D7-Pad2)") (class "Default")
      (node (ref "D7") (pin "2") (pinfunction "2_2") (pintype "power_in"))
      (node (ref "T2") (pin "12") (pinfunction "12_12") (pintype "passive"))
    )
    (net (code "36") (name "Net-(D8-Pad2)") (class "Default")
      (node (ref "D8") (pin "2") (pinfunction "2_2") (pintype "power_in"))
      (node (ref "T2") (pin "7") (pinfunction "7_7") (pintype "passive"))
    )
    (net (code "37") (name "Net-(D10-Pad2)") (class "Default")
      (node (ref "D10") (pin "2") (pinfunction "2_2") (pintype "power_in"))
      (node (ref "R25") (pin "2") (pinfunction "2_2") (pintype "passive"))
    )
    (net (code "38") (name "Net-(D11-Pad2)") (class "Default")
      (node (ref "D11") (pin "2") (pinfunction "2_2") (pintype "power_in"))
      (node (ref "R23") (pin "2") (pinfunction "2_2") (pintype "passive"))
    )
    (net (code "39") (name "Net-(L1-Pad1)") (class "Default")
      (node (ref "L1") (pin "1") (pinfunction "1_1") (pintype "passive"))
      (node (ref "L2") (pin "1") (pinfunction "1_1") (pintype "passive"))
      (node (ref "T1") (pin "7") (pinfunction "7_7") (pintype "passive"))
    )
    (net (code "40") (name "Net-(L4-Pad2)") (class "Default")
      (node (ref "L4") (pin "2") (pinfunction "2_2") (pintype "passive"))
      (node (ref "T2") (pin "10") (pinfunction "10_10") (pintype "passive"))
      (node (ref "T2") (pin "9") (pinfunction "9_9") (pintype "passive"))
    )
    (net (code "41") (name "Net-(Q1-DRAIN)") (class "Default")
      (node (ref "D2") (pin "1") (pinfunction "1_1") (pintype "power_in"))
      (node (ref "D2") (pin "3") (pinfunction "3_3") (pintype "power_in"))
      (node (ref "D4") (pin "1") (pinfunction "1_1") (pintype "power_in"))
      (node (ref "L1") (pin "2") (pinfunction "2_2") (pintype "passive"))
      (node (ref "Q1") (pin "2") (pinfunction "DRAIN_2") (pintype "passive"))
      (node (ref "Q2") (pin "2") (pinfunction "DRAIN_2") (pintype "passive"))
    )
    (net (code "42") (name "Net-(Q3-B)") (class "Default")
      (node (ref "C3") (pin "2") (pinfunction "2_2") (pintype "passive"))
      (node (ref "Q3") (pin "1") (pinfunction "B_1") (pintype "power_in"))
      (node (ref "U1") (pin "7") (pinfunction "CT_7") (pintype "input"))
    )
    (net (code "43") (name "Net-(Q3-E)") (class "Default")
      (node (ref "Q3") (pin "2") (pinfunction "E_2") (pintype "power_in"))
      (node (ref "R4") (pin "2") (pinfunction "2_2") (pintype "passive"))
    )
    (net (code "44") (name "Net-(R17-Pad1)") (class "Default")
      (node (ref "R17") (pin "1") (pinfunction "1_1") (pintype "passive"))
      (node (ref "R19") (pin "2") (pinfunction "2_2") (pintype "passive"))
    )
    (net (code "45") (name "Net-(R18-Pad1)") (class "Default")
      (node (ref "R18") (pin "1") (pinfunction "1_1") (pintype "passive"))
      (node (ref "R21") (pin "2") (pinfunction "2_2") (pintype "passive"))
    )
    (net (code "46") (name "Net-(U1-ADS)") (class "Default")
      (node (ref "R3") (pin "1") (pinfunction "1_1") (pintype "passive"))
      (node (ref "R5") (pin "1") (pinfunction "1_1") (pintype "passive"))
      (node (ref "U1") (pin "11") (pinfunction "ADS_11") (pintype "input"))
    )
    (net (code "47") (name "Net-(U1-DELAB)") (class "Default")
      (node (ref "R7") (pin "2") (pinfunction "2_2") (pintype "passive"))
      (node (ref "U1") (pin "9") (pinfunction "DELAB_9") (pintype "output"))
    )
    (net (code "48") (name "Net-(U1-DELCD)") (class "Default")
      (node (ref "R10") (pin "2") (pinfunction "2_2") (pintype "passive"))
      (node (ref "U1") (pin "10") (pinfunction "DELCD_10") (pintype "output"))
    )
    (net (code "49") (name "Net-(U1-RT)") (class "Default")
      (node (ref "R14") (pin "2") (pinfunction "2_2") (pintype "passive"))
      (node (ref "U1") (pin "8") (pinfunction "RT_8") (pintype "input"))
    )
    (net (code "50") (name "Net-(U1-SS{slash}DISB)") (class "Default")
      (node (ref "C8") (pin "2") (pinfunction "2_2") (pintype "passive"))
      (node (ref "U1") (pin "19") (pinfunction "SS/DISB_19") (pintype "input"))
    )
    (net (code "51") (name "Net-(U2-A)") (class "Default")
      (node (ref "R18") (pin "2") (pinfunction "2_2") (pintype "passive"))
      (node (ref "R8") (pin "1") (pinfunction "1_1") (pintype "passive"))
      (node (ref "U2") (pin "1") (pinfunction "A_1") (pintype "passive"))
    )
    (net (code "52") (name "Net-(U2-K)") (class "Default")
      (node (ref "R17") (pin "2") (pinfunction "2_2") (pintype "passive"))
      (node (ref "U2") (pin "2") (pinfunction "K_2") (pintype "passive"))
    )
    (net (code "53") (name "Net-(U4-HB)") (class "Default")
      (node (ref "C19") (pin "2") (pinfunction "2_2") (pintype "passive"))
      (node (ref "D11") (pin "1") (pinfunction "1_1") (pintype "power_in"))
      (node (ref "U4") (pin "13") (pinfunction "HB_13") (pintype "passive"))
    )
    (net (code "54") (name "Net-(U4-HI)") (class "Default")
      (node (ref "C21") (pin "2") (pinfunction "2_2") (pintype "passive"))
      (node (ref "R30") (pin "2") (pinfunction "2_2") (pintype "passive"))
      (node (ref "U4") (pin "1") (pinfunction "HI_1") (pintype "passive"))
    )
    (net (code "55") (name "Net-(U4-LI)") (class "Default")
      (node (ref "C23") (pin "2") (pinfunction "2_2") (pintype "passive"))
      (node (ref "R36") (pin "2") (pinfunction "2_2") (pintype "passive"))
      (node (ref "U4") (pin "2") (pinfunction "LI_2") (pintype "passive"))
    )
    (net (code "56") (name "Net-(U4-LO)") (class "Default")
      (node (ref "R32") (pin "1") (pinfunction "1_1") (pintype "passive"))
      (node (ref "U4") (pin "6") (pinfunction "LO_6") (pintype "passive"))
    )
    (net (code "57") (name "Net-(U5-HB)") (class "Default")
      (node (ref "C20") (pin "2") (pinfunction "2_2") (pintype "passive"))
      (node (ref "D10") (pin "1") (pinfunction "1_1") (pintype "power_in"))
      (node (ref "U5") (pin "13") (pinfunction "HB_13") (pintype "passive"))
    )
    (net (code "58") (name "Net-(U5-HI)") (class "Default")
      (node (ref "C22") (pin "2") (pinfunction "2_2") (pintype "passive"))
      (node (ref "R31") (pin "2") (pinfunction "2_2") (pintype "passive"))
      (node (ref "U5") (pin "1") (pinfunction "HI_1") (pintype "passive"))
    )
    (net (code "59") (name "Net-(U5-LI)") (class "Default")
      (node (ref "C24") (pin "2") (pinfunction "2_2") (pintype "passive"))
      (node (ref "R37") (pin "2") (pinfunction "2_2") (pintype "passive"))
      (node (ref "U5") (pin "2") (pinfunction "LI_2") (pintype "passive"))
    )
    (net (code "60") (name "Net-(U5-LO)") (class "Default")
      (node (ref "R34") (pin "1") (pinfunction "1_1") (pintype "passive"))
      (node (ref "U5") (pin "6") (pinfunction "LO_6") (pintype "passive"))
    )
    (net (code "61") (name "unconnected-(H1-Pad2)") (class "Default")
      (node (ref "H1") (pin "2") (pinfunction "2_2") (pintype "passive"))
    )
    (net (code "62") (name "unconnected-(H2-Pad2)") (class "Default")
      (node (ref "H2") (pin "2") (pinfunction "2_2") (pintype "passive"))
    )
    (net (code "63") (name "unconnected-(H3-Pad2)") (class "Default")
      (node (ref "H3") (pin "2") (pinfunction "2_2") (pintype "passive"))
    )
    (net (code "64") (name "unconnected-(U1-SYNC-Pad6)") (class "Default")
      (node (ref "U1") (pin "6") (pinfunction "SYNC_6") (pintype "bidirectional+no_connect"))
    )
    (net (code "65") (name "unconnected-(U2-B-Pad6)") (class "Default")
      (node (ref "U2") (pin "6") (pinfunction "B_6") (pintype "passive+no_connect"))
    )
    (net (code "66") (name "unconnected-(U2-NC-Pad3)") (class "Default")
      (node (ref "U2") (pin "3") (pinfunction "NC_3") (pintype "passive+no_connect"))
    )
    (net (code "67") (name "unconnected-(U4-EN{slash}NC-Pad4)") (class "Default")
      (node (ref "U4") (pin "4") (pinfunction "EN/NC_4") (pintype "passive+no_connect"))
    )
    (net (code "68") (name "unconnected-(U4-NC_1-Pad8)") (class "Default")
      (node (ref "U4") (pin "8") (pinfunction "NC_1_8") (pintype "passive+no_connect"))
    )
    (net (code "69") (name "unconnected-(U4-NC_2-Pad9)") (class "Default")
      (node (ref "U4") (pin "9") (pinfunction "NC_2_9") (pintype "passive+no_connect"))
    )
    (net (code "70") (name "unconnected-(U4-NC_3-Pad10)") (class "Default")
      (node (ref "U4") (pin "10") (pinfunction "NC_3_10") (pintype "passive+no_connect"))
    )
    (net (code "71") (name "unconnected-(U4-NC_4-Pad14)") (class "Default")
      (node (ref "U4") (pin "14") (pinfunction "NC_4_14") (pintype "passive+no_connect"))
    )
    (net (code "72") (name "unconnected-(U5-EN{slash}NC-Pad4)") (class "Default")
      (node (ref "U5") (pin "4") (pinfunction "EN/NC_4") (pintype "passive+no_connect"))
    )
    (net (code "73") (name "unconnected-(U5-NC_1-Pad8)") (class "Default")
      (node (ref "U5") (pin "8") (pinfunction "NC_1_8") (pintype "passive+no_connect"))
    )
    (net (code "74") (name "unconnected-(U5-NC_2-Pad9)") (class "Default")
      (node (ref "U5") (pin "9") (pinfunction "NC_2_9") (pintype "passive+no_connect"))
    )
    (net (code "75") (name "unconnected-(U5-NC_3-Pad10)") (class "Default")
      (node (ref "U5") (pin "10") (pinfunction "NC_3_10") (pintype "passive+no_connect"))
    )
    (net (code "76") (name "unconnected-(U5-NC_4-Pad14)") (class "Default")
      (node (ref "U5") (pin "14") (pinfunction "NC_4_14") (pintype "passive+no_connect"))
    )
  )
)
